# beovox-poe.net
KiCad netlist of a schematic drawn in Altium Designer
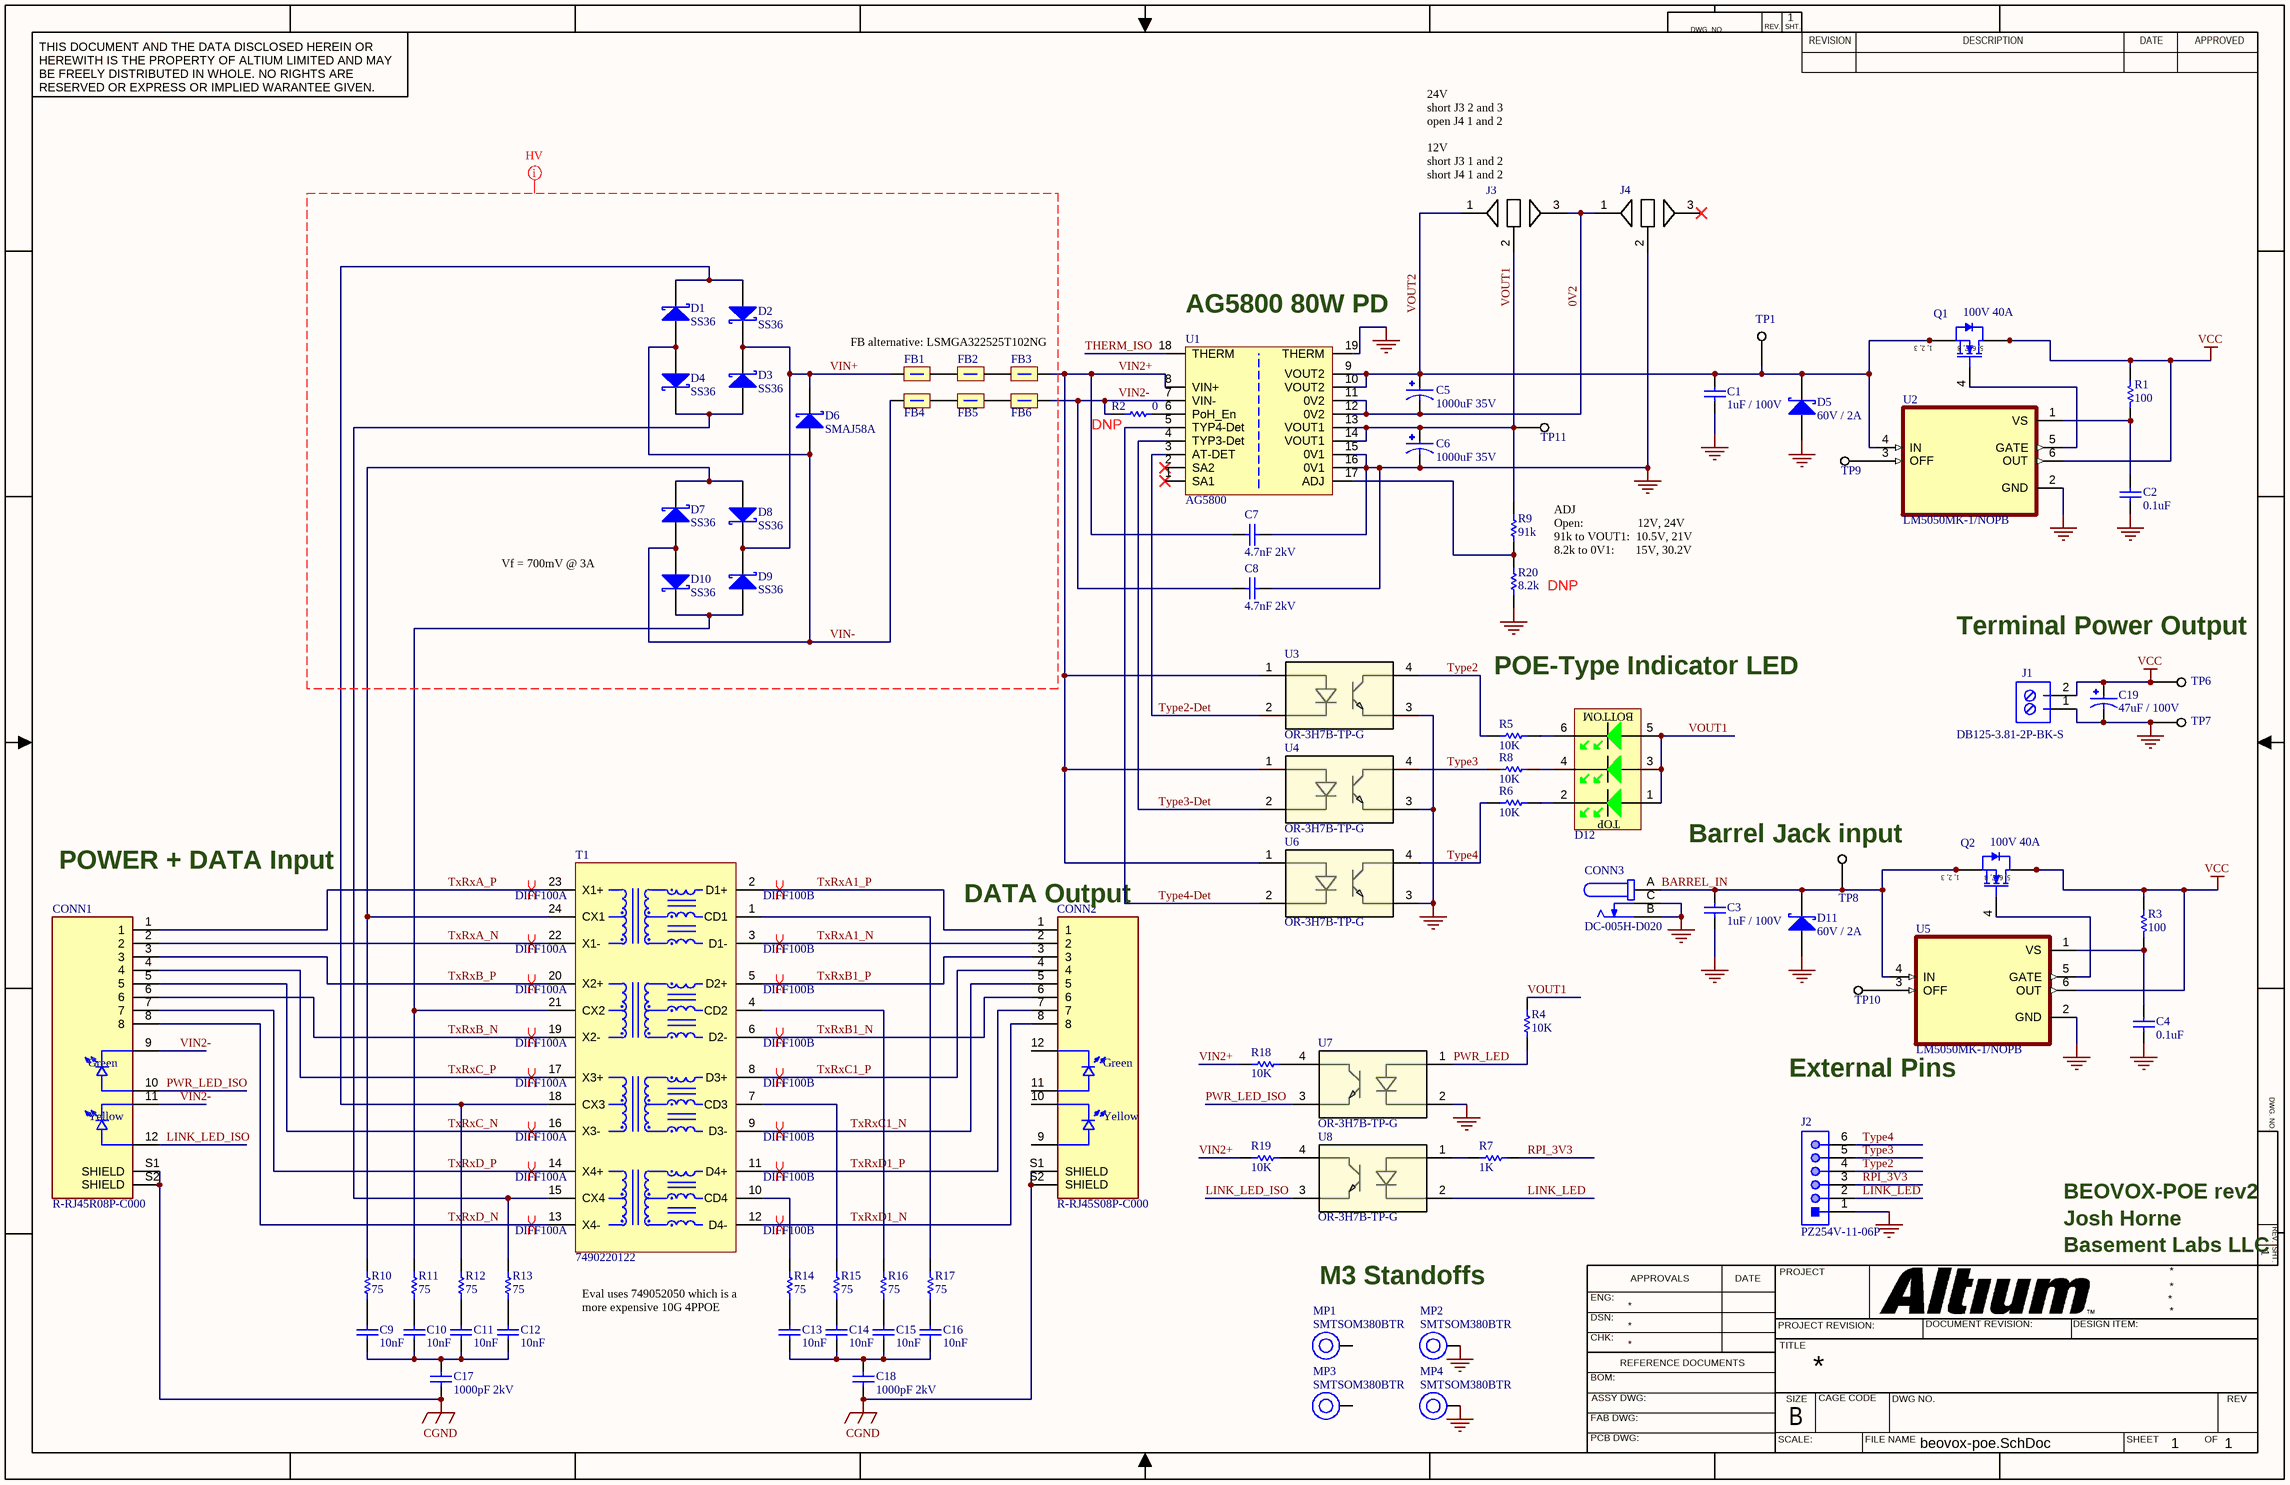
[diagram p0: beovox-poe.SchDoc]

(export (version "E")
  (design (tool "Eeschema 10.0.6"))
  (components
    (comp (ref "C1")
      (value "1uF / 100V")
      (footprint "CAP_1210")
      (description "1210 1 uF 100 V ±10% Tolerance X7R SMT Multilayer Ceramic Capacitor")
      (fields
        (field (name "MANUFACTURER") "Murata")
        (field (name "MANUFACTURER PART NUMBER") "GRM32ER72A105KA01L")
      )
      (libsource (lib "josh-lib") (part "GRM32ER72A105KA01L"))
    )
    (comp (ref "C2")
      (value "0.1uF")
      (footprint "CAP_0603_SK")
      (description "0603 0.1 uF 100 V ±10% Tolerance X7R Multilayer Ceramic Capacitor")
      (fields
        (field (name "MANUFACTURER") "Yageo")
        (field (name "MANUFACTURER PART NUMBER") "CC0603KRX7R0BB104")
      )
      (libsource (lib "josh-lib") (part "CC0603KRX7R0BB104"))
    )
    (comp (ref "C3")
      (value "1uF / 100V")
      (footprint "CAP_1210")
      (description "1210 1 uF 100 V ±10% Tolerance X7R SMT Multilayer Ceramic Capacitor")
      (fields
        (field (name "MANUFACTURER") "Murata")
        (field (name "MANUFACTURER PART NUMBER") "GRM32ER72A105KA01L")
      )
      (libsource (lib "josh-lib") (part "GRM32ER72A105KA01L"))
    )
    (comp (ref "C4")
      (value "0.1uF")
      (footprint "CAP_0603_SK")
      (description "0603 0.1 uF 100 V ±10% Tolerance X7R Multilayer Ceramic Capacitor")
      (fields
        (field (name "MANUFACTURER") "Yageo")
        (field (name "MANUFACTURER PART NUMBER") "CC0603KRX7R0BB104")
      )
      (libsource (lib "josh-lib") (part "CC0603KRX7R0BB104"))
    )
    (comp (ref "C5")
      (value "1000uF 35V")
      (footprint "CAP_TH_5_10X20")
      (description "1000uF 35V ±20% Plugin,D10xL20mm Aluminum Electrolytic Capacitors - Leaded ROHS")
      (fields
        (field (name "MANUFACTURER") "AISHI")
        (field (name "MANUFACTURER PART NUMBER") "ERR1VM102G20OT")
      )
      (libsource (lib "josh-lib") (part "ERR1VM102G20OT"))
    )
    (comp (ref "C6")
      (value "1000uF 35V")
      (footprint "CAP_TH_5_10X20")
      (description "1000uF 35V ±20% Plugin,D10xL20mm Aluminum Electrolytic Capacitors - Leaded ROHS")
      (fields
        (field (name "MANUFACTURER") "AISHI")
        (field (name "MANUFACTURER PART NUMBER") "ERR1VM102G20OT")
      )
      (libsource (lib "josh-lib") (part "ERR1VM102G20OT"))
    )
    (comp (ref "C7")
      (value "4.7nF 2kV")
      (footprint "CAP_1206_SK")
      (description "2kV 4700pF X7R ±10% 1206 Multilayer Ceramic Capacitors MLCC - SMD/SMT ROHS")
      (fields
        (field (name "MANUFACTURER") "FH (Guangdong Fenghua Advanced Tech)")
        (field (name "MANUFACTURER PART NUMBER") "1206B472K202NT")
      )
      (libsource (lib "josh-lib") (part "1206B472K202NT"))
    )
    (comp (ref "C8")
      (value "4.7nF 2kV")
      (footprint "CAP_1206_SK")
      (description "2kV 4700pF X7R ±10% 1206 Multilayer Ceramic Capacitors MLCC - SMD/SMT ROHS")
      (fields
        (field (name "MANUFACTURER") "FH (Guangdong Fenghua Advanced Tech)")
        (field (name "MANUFACTURER PART NUMBER") "1206B472K202NT")
      )
      (libsource (lib "josh-lib") (part "1206B472K202NT"))
    )
    (comp (ref "C9")
      (value "10nF")
      (footprint "CAP_0603_SK")
      (description "Multilayer Ceramic Capacitor, 0.01 F, 10%, X7R, 100 V, 0603 [1608 Metric] Rohs Compliant: Yes")
      (fields
        (field (name "MANUFACTURER") "Walsin Technologies")
        (field (name "MANUFACTURER PART NUMBER") "0603B103K101CT")
      )
      (libsource (lib "josh-lib") (part "0603B103K101CT"))
    )
    (comp (ref "C10")
      (value "10nF")
      (footprint "CAP_0603_SK")
      (description "Multilayer Ceramic Capacitor, 0.01 F, 10%, X7R, 100 V, 0603 [1608 Metric] Rohs Compliant: Yes")
      (fields
        (field (name "MANUFACTURER") "Walsin Technologies")
        (field (name "MANUFACTURER PART NUMBER") "0603B103K101CT")
      )
      (libsource (lib "josh-lib") (part "0603B103K101CT"))
    )
    (comp (ref "C11")
      (value "10nF")
      (footprint "CAP_0603_SK")
      (description "Multilayer Ceramic Capacitor, 0.01 F, 10%, X7R, 100 V, 0603 [1608 Metric] Rohs Compliant: Yes")
      (fields
        (field (name "MANUFACTURER") "Walsin Technologies")
        (field (name "MANUFACTURER PART NUMBER") "0603B103K101CT")
      )
      (libsource (lib "josh-lib") (part "0603B103K101CT"))
    )
    (comp (ref "C12")
      (value "10nF")
      (footprint "CAP_0603_SK")
      (description "Multilayer Ceramic Capacitor, 0.01 F, 10%, X7R, 100 V, 0603 [1608 Metric] Rohs Compliant: Yes")
      (fields
        (field (name "MANUFACTURER") "Walsin Technologies")
        (field (name "MANUFACTURER PART NUMBER") "0603B103K101CT")
      )
      (libsource (lib "josh-lib") (part "0603B103K101CT"))
    )
    (comp (ref "C13")
      (value "10nF")
      (footprint "CAP_0603_SK")
      (description "Multilayer Ceramic Capacitor, 0.01 F, 10%, X7R, 100 V, 0603 [1608 Metric] Rohs Compliant: Yes")
      (fields
        (field (name "MANUFACTURER") "Walsin Technologies")
        (field (name "MANUFACTURER PART NUMBER") "0603B103K101CT")
      )
      (libsource (lib "josh-lib") (part "0603B103K101CT"))
    )
    (comp (ref "C14")
      (value "10nF")
      (footprint "CAP_0603_SK")
      (description "Multilayer Ceramic Capacitor, 0.01 F, 10%, X7R, 100 V, 0603 [1608 Metric] Rohs Compliant: Yes")
      (fields
        (field (name "MANUFACTURER") "Walsin Technologies")
        (field (name "MANUFACTURER PART NUMBER") "0603B103K101CT")
      )
      (libsource (lib "josh-lib") (part "0603B103K101CT"))
    )
    (comp (ref "C15")
      (value "10nF")
      (footprint "CAP_0603_SK")
      (description "Multilayer Ceramic Capacitor, 0.01 F, 10%, X7R, 100 V, 0603 [1608 Metric] Rohs Compliant: Yes")
      (fields
        (field (name "MANUFACTURER") "Walsin Technologies")
        (field (name "MANUFACTURER PART NUMBER") "0603B103K101CT")
      )
      (libsource (lib "josh-lib") (part "0603B103K101CT"))
    )
    (comp (ref "C16")
      (value "10nF")
      (footprint "CAP_0603_SK")
      (description "Multilayer Ceramic Capacitor, 0.01 F, 10%, X7R, 100 V, 0603 [1608 Metric] Rohs Compliant: Yes")
      (fields
        (field (name "MANUFACTURER") "Walsin Technologies")
        (field (name "MANUFACTURER PART NUMBER") "0603B103K101CT")
      )
      (libsource (lib "josh-lib") (part "0603B103K101CT"))
    )
    (comp (ref "C17")
      (value "1000pF 2kV")
      (footprint "CAP_1206_SK")
      (description "Multilayer Ceramic Capacitor, 1000 pF, 2000 V, ± 10%, X7R, 1206 [3216 Metric]")
      (fields
        (field (name "MANUFACTURER") "Yageo")
        (field (name "MANUFACTURER PART NUMBER") "CC1206KKX7RDBB102")
      )
      (libsource (lib "josh-lib") (part "CC1206KKX7RDBB102"))
    )
    (comp (ref "C18")
      (value "1000pF 2kV")
      (footprint "CAP_1206_SK")
      (description "Multilayer Ceramic Capacitor, 1000 pF, 2000 V, ± 10%, X7R, 1206 [3216 Metric]")
      (fields
        (field (name "MANUFACTURER") "Yageo")
        (field (name "MANUFACTURER PART NUMBER") "CC1206KKX7RDBB102")
      )
      (libsource (lib "josh-lib") (part "CC1206KKX7RDBB102"))
    )
    (comp (ref "C19")
      (value "47uF / 100V")
      (footprint "CAP_TH_3.5_8_12")
      (description "47uF 100V ±20% Plugin,D8xL12mm Aluminum Electrolytic Capacitors - Leaded ROHS")
      (fields
        (field (name "MANUFACTURER") "AISHI(Aihua Group)")
        (field (name "MANUFACTURER PART NUMBER") "ERS1KM470F12OT")
      )
      (libsource (lib "josh-lib") (part "ERS1KM470F12OT"))
    )
    (comp (ref "CONN1")
      (value "R-RJ45R08P-C000")
      (footprint "R-RJ45R08P-C000")
      (fields (field (name "MANUFACTURER") "Ckmtw"))
      (libsource (lib "josh-lib") (part "R-RJ45R08P-C000"))
    )
    (comp (ref "CONN2")
      (value "R-RJ45S08P-C000")
      (footprint "CONN_RJ45_R-RJ45S08P-C000")
      (fields (field (name "MANUFACTURER") "Ckmtw(Shenzhen Cankemeng)"))
      (libsource (lib "josh-lib") (part "R-RJ45S08P-C000"))
    )
    (comp (ref "CONN3")
      (value "DC-005H-D020")
      (footprint "TENSILITY_54-00166")
      (description "Right-Angle DC Power Receptacle -30℃~+85℃ 2mm 5.8mm 7A 35V Plugin AC/DC Power Connectors ROHS")
      (fields (field (name "MANUFACTURER") "G-Switch"))
      (libsource (lib "josh-lib") (part "DC-005H-D020"))
    )
    (comp (ref "D1")
      (value "SS36")
      (footprint "DIOD-SMA-2_V")
      (description "60V 700mV@3A 3A SMA(DO-214AC) Schottky Barrier Diodes (SBD) ROHS")
      (fields (field (name "MANUFACTURER") "MDD"))
      (libsource (lib "josh-lib") (part "SS36"))
    )
    (comp (ref "D2")
      (value "SS36")
      (footprint "DIOD-SMA-2_V")
      (description "60V 700mV@3A 3A SMA(DO-214AC) Schottky Barrier Diodes (SBD) ROHS")
      (fields (field (name "MANUFACTURER") "MDD"))
      (libsource (lib "josh-lib") (part "SS36"))
    )
    (comp (ref "D3")
      (value "SS36")
      (footprint "DIOD-SMA-2_V")
      (description "60V 700mV@3A 3A SMA(DO-214AC) Schottky Barrier Diodes (SBD) ROHS")
      (fields (field (name "MANUFACTURER") "MDD"))
      (libsource (lib "josh-lib") (part "SS36"))
    )
    (comp (ref "D4")
      (value "SS36")
      (footprint "DIOD-SMA-2_V")
      (description "60V 700mV@3A 3A SMA(DO-214AC) Schottky Barrier Diodes (SBD) ROHS")
      (fields (field (name "MANUFACTURER") "MDD"))
      (libsource (lib "josh-lib") (part "SS36"))
    )
    (comp (ref "D5")
      (value "60V / 2A")
      (footprint "DIOD-B360A_V")
      (description "VR=60V IF=2A 200pF")
      (fields (field (name "MANUFACTURER") "Diodes") (field (name "MANUFACTURER PART NUMBER") "B260-13-F"))
      (libsource (lib "josh-lib") (part "B260-13-F"))
    )
    (comp (ref "D6")
      (value "SMAJ58A")
      (footprint "DIOD-SMA-2_V")
      (description "4.3A 400W 93.6V 64.4V 58V SMA(DO-214AC) TVS ROHS")
      (fields (field (name "MANUFACTURER") "GOODWORK"))
      (libsource (lib "josh-lib") (part "SMAJ58A"))
    )
    (comp (ref "D7")
      (value "SS36")
      (footprint "DIOD-SMA-2_V")
      (description "60V 700mV@3A 3A SMA(DO-214AC) Schottky Barrier Diodes (SBD) ROHS")
      (fields (field (name "MANUFACTURER") "MDD"))
      (libsource (lib "josh-lib") (part "SS36"))
    )
    (comp (ref "D8")
      (value "SS36")
      (footprint "DIOD-SMA-2_V")
      (description "60V 700mV@3A 3A SMA(DO-214AC) Schottky Barrier Diodes (SBD) ROHS")
      (fields (field (name "MANUFACTURER") "MDD"))
      (libsource (lib "josh-lib") (part "SS36"))
    )
    (comp (ref "D9")
      (value "SS36")
      (footprint "DIOD-SMA-2_V")
      (description "60V 700mV@3A 3A SMA(DO-214AC) Schottky Barrier Diodes (SBD) ROHS")
      (fields (field (name "MANUFACTURER") "MDD"))
      (libsource (lib "josh-lib") (part "SS36"))
    )
    (comp (ref "D10")
      (value "SS36")
      (footprint "DIOD-SMA-2_V")
      (description "60V 700mV@3A 3A SMA(DO-214AC) Schottky Barrier Diodes (SBD) ROHS")
      (fields (field (name "MANUFACTURER") "MDD"))
      (libsource (lib "josh-lib") (part "SS36"))
    )
    (comp (ref "D11")
      (value "60V / 2A")
      (footprint "DIOD-B360A_V")
      (description "VR=60V IF=2A 200pF")
      (fields (field (name "MANUFACTURER") "Diodes") (field (name "MANUFACTURER PART NUMBER") "B260-13-F"))
      (libsource (lib "josh-lib") (part "B260-13-F"))
    )
    (comp (ref "D12")
      (value "3 Diode Vertical LED Green")
      (footprint "MHK33147CGBTD")
      (description "20mA 30mcd 雾状绿透镜 -40℃~+85℃ 568nm Green 60° 2.6V DIP-6-2.54mm Light Emitting Diodes (LED) ROHS")
      (fields
        (field (name "MANUFACTURER") "MEIHUA")
        (field (name "MANUFACTURER PART NUMBER") "MHK33147CGBTD")
      )
      (libsource (lib "josh-lib") (part "MHK33147CGBTD"))
    )
    (comp (ref "FB1")
      (value "MPZ2012S601AT000")
      (footprint "FB0805")
      (description "Ferrite Beads Multi-Layer Power 600Ohm 25% 100MHz 2A 100mOhm DCR 0805 T/R")
      (fields (field (name "MANUFACTURER") "TDK") (field (name "TOLERANCE") "25%"))
      (libsource (lib "josh-lib") (part "MPZ2012S601AT000"))
    )
    (comp (ref "FB2")
      (value "MPZ2012S601AT000")
      (footprint "FB0805")
      (description "Ferrite Beads Multi-Layer Power 600Ohm 25% 100MHz 2A 100mOhm DCR 0805 T/R")
      (fields (field (name "MANUFACTURER") "TDK") (field (name "TOLERANCE") "25%"))
      (libsource (lib "josh-lib") (part "MPZ2012S601AT000"))
    )
    (comp (ref "FB3")
      (value "MPZ2012S601AT000")
      (footprint "FB0805")
      (description "Ferrite Beads Multi-Layer Power 600Ohm 25% 100MHz 2A 100mOhm DCR 0805 T/R")
      (fields (field (name "MANUFACTURER") "TDK") (field (name "TOLERANCE") "25%"))
      (libsource (lib "josh-lib") (part "MPZ2012S601AT000"))
    )
    (comp (ref "FB4")
      (value "MPZ2012S601AT000")
      (footprint "FB0805")
      (description "Ferrite Beads Multi-Layer Power 600Ohm 25% 100MHz 2A 100mOhm DCR 0805 T/R")
      (fields (field (name "MANUFACTURER") "TDK") (field (name "TOLERANCE") "25%"))
      (libsource (lib "josh-lib") (part "MPZ2012S601AT000"))
    )
    (comp (ref "FB5")
      (value "MPZ2012S601AT000")
      (footprint "FB0805")
      (description "Ferrite Beads Multi-Layer Power 600Ohm 25% 100MHz 2A 100mOhm DCR 0805 T/R")
      (fields (field (name "MANUFACTURER") "TDK") (field (name "TOLERANCE") "25%"))
      (libsource (lib "josh-lib") (part "MPZ2012S601AT000"))
    )
    (comp (ref "FB6")
      (value "MPZ2012S601AT000")
      (footprint "FB0805")
      (description "Ferrite Beads Multi-Layer Power 600Ohm 25% 100MHz 2A 100mOhm DCR 0805 T/R")
      (fields (field (name "MANUFACTURER") "TDK") (field (name "TOLERANCE") "25%"))
      (libsource (lib "josh-lib") (part "MPZ2012S601AT000"))
    )
    (comp (ref "J1")
      (value "DB125-3.81-2P-BK-S")
      (footprint "TERM_2x1_3.81_BLK")
      (description "1x2P 10A -40℃~+105℃ 300V Black 16~26 Straight 3.81mm 0.5~1 1 2 Plugin,P=3.81mm Screw terminal ROHS")
      (fields (field (name "MANUFACTURER") "Dorabo"))
      (libsource (lib "josh-lib") (part "DB125-3.81-2P-BK-S"))
    )
    (comp (ref "J2")
      (value "PZ254V-11-06P")
      (footprint "HDR_MALE_1X6_2.54")
      (fields (field (name "MANUFACTURER") "XFCN"))
      (libsource (lib "josh-lib") (part "PZ254V-11-06P"))
    )
    (comp (ref "J3")
      (value "JUMPER")
      (footprint "SOLDER_JUMPER_3 large")
      (libsource (lib "josh-lib") (part "Solder_Jumper_3"))
    )
    (comp (ref "J4")
      (value "JUMPER")
      (footprint "SOLDER_JUMPER_3 large")
      (libsource (lib "josh-lib") (part "Solder_Jumper_3"))
    )
    (comp (ref "MP1")
      (value "SMTSOM380BTR")
      (footprint "SMTSOM380_PlatedScrew")
      (description "M3 Round Nut 8mm height")
      (fields (field (name "MANUFACTURER") "YIYUAN"))
      (libsource (lib "josh-lib") (part "SMTSOM380BTR"))
    )
    (comp (ref "MP2")
      (value "SMTSOM380BTR")
      (footprint "SMTSOM380_PlatedScrew")
      (description "M3 Round Nut 8mm height")
      (fields (field (name "MANUFACTURER") "YIYUAN"))
      (libsource (lib "josh-lib") (part "SMTSOM380BTR"))
    )
    (comp (ref "MP3")
      (value "SMTSOM380BTR")
      (footprint "SMTSOM380_PlatedScrew")
      (description "M3 Round Nut 8mm height")
      (fields (field (name "MANUFACTURER") "YIYUAN"))
      (libsource (lib "josh-lib") (part "SMTSOM380BTR"))
    )
    (comp (ref "MP4")
      (value "SMTSOM380BTR")
      (footprint "SMTSOM380_PlatedScrew")
      (description "M3 Round Nut 8mm height")
      (fields (field (name "MANUFACTURER") "YIYUAN"))
      (libsource (lib "josh-lib") (part "SMTSOM380BTR"))
    )
    (comp (ref "Q1")
      (value "100V 40A")
      (footprint "TRANS_8PowerTDFN")
      (description "BSZ097xx Series 100 V 40 A 9.7 mOhm OptiMOS5 Power-MOSFET - TSDSON-8 FL")
      (fields
        (field (name "MANUFACTURER") "Infineon")
        (field (name "MANUFACTURER PART NUMBER") "BSZ097N10NS5ATMA1")
      )
      (libsource (lib "josh-lib") (part "BSZ097N10NS5ATMA1"))
    )
    (comp (ref "Q2")
      (value "100V 40A")
      (footprint "TRANS_8PowerTDFN")
      (description "BSZ097xx Series 100 V 40 A 9.7 mOhm OptiMOS5 Power-MOSFET - TSDSON-8 FL")
      (fields
        (field (name "MANUFACTURER") "Infineon")
        (field (name "MANUFACTURER PART NUMBER") "BSZ097N10NS5ATMA1")
      )
      (libsource (lib "josh-lib") (part "BSZ097N10NS5ATMA1"))
    )
    (comp (ref "R1")
      (value "100")
      (footprint "RES_0603")
      (description "Res Thick Film 0603 100 Ohm 1% 1/10W ±100ppm/°C Molded SMD Paper T/R")
      (fields
        (field (name "MANUFACTURER") "Yageo")
        (field (name "MANUFACTURER PART NUMBER") "RC0603FR-07100RL")
      )
      (libsource (lib "josh-lib") (part "RC0603FR-07100RL"))
    )
    (comp (ref "R2")
      (value "0")
      (footprint "RES_0805")
      (description "Surface Mount Thick Film Resistor, RC Series, 125 mW, - 5%, 150 V, 0805 [2012 Metric]")
      (fields
        (field (name "MANUFACTURER") "Yageo")
        (field (name "MANUFACTURER PART NUMBER") "RC0805JR-070RL")
      )
      (libsource (lib "josh-lib") (part "RC0805JR-070RL"))
    )
    (comp (ref "R3")
      (value "100")
      (footprint "RES_0603")
      (description "Res Thick Film 0603 100 Ohm 1% 1/10W ±100ppm/°C Molded SMD Paper T/R")
      (fields
        (field (name "MANUFACTURER") "Yageo")
        (field (name "MANUFACTURER PART NUMBER") "RC0603FR-07100RL")
      )
      (libsource (lib "josh-lib") (part "RC0603FR-07100RL"))
    )
    (comp (ref "R4")
      (value "10K")
      (footprint "RES_0603")
      (description "RES SMD 10K OHM 1% 1/10W 0603")
      (fields
        (field (name "MANUFACTURER") "Panasonic")
        (field (name "MANUFACTURER PART NUMBER") "ERJ3EKF1002V")
      )
      (libsource (lib "josh-lib") (part "ERJ3EKF1002V"))
    )
    (comp (ref "R5")
      (value "10K")
      (footprint "RES_0603")
      (description "RES SMD 10K OHM 1% 1/10W 0603")
      (fields
        (field (name "MANUFACTURER") "Panasonic")
        (field (name "MANUFACTURER PART NUMBER") "ERJ3EKF1002V")
      )
      (libsource (lib "josh-lib") (part "ERJ3EKF1002V"))
    )
    (comp (ref "R6")
      (value "10K")
      (footprint "RES_0603")
      (description "RES SMD 10K OHM 1% 1/10W 0603")
      (fields
        (field (name "MANUFACTURER") "Panasonic")
        (field (name "MANUFACTURER PART NUMBER") "ERJ3EKF1002V")
      )
      (libsource (lib "josh-lib") (part "ERJ3EKF1002V"))
    )
    (comp (ref "R7")
      (value "1K")
      (footprint "RES_0603")
      (description "Res Thick Film 0603 1K Ohm 1% 1/10W ±100ppm/°C Molded SMD SMD Paper T/R")
      (fields
        (field (name "MANUFACTURER") "Yageo")
        (field (name "MANUFACTURER PART NUMBER") "RC0603FR-071KL")
      )
      (libsource (lib "josh-lib") (part "RC0603FR-071KL"))
    )
    (comp (ref "R8")
      (value "10K")
      (footprint "RES_0603")
      (description "RES SMD 10K OHM 1% 1/10W 0603")
      (fields
        (field (name "MANUFACTURER") "Panasonic")
        (field (name "MANUFACTURER PART NUMBER") "ERJ3EKF1002V")
      )
      (libsource (lib "josh-lib") (part "ERJ3EKF1002V"))
    )
    (comp (ref "R9")
      (value "91k")
      (footprint "RES_0603")
      (description "SMD Chip Resistor, 91 kOhm, ± 1%, 100 mW, 0603 [1608 Metric], Thick Film, General Purpose")
      (fields
        (field (name "MANUFACTURER") "Yageo")
        (field (name "MANUFACTURER PART NUMBER") "RC0603FR-0791KL")
      )
      (libsource (lib "josh-lib") (part "RC0603FR-0791KL"))
    )
    (comp (ref "R10")
      (value "75")
      (footprint "RES_0603")
      (description "SMD Chip Resistor, 75 Ohm, ± 1%, 100 mW, 0603 [1608 Metric], Thick Film, General Purpose")
      (fields
        (field (name "MANUFACTURER") "Yageo")
        (field (name "MANUFACTURER PART NUMBER") "RC0603FR-0775RL")
      )
      (libsource (lib "josh-lib") (part "RC0603FR-0775RL"))
    )
    (comp (ref "R11")
      (value "75")
      (footprint "RES_0603")
      (description "SMD Chip Resistor, 75 Ohm, ± 1%, 100 mW, 0603 [1608 Metric], Thick Film, General Purpose")
      (fields
        (field (name "MANUFACTURER") "Yageo")
        (field (name "MANUFACTURER PART NUMBER") "RC0603FR-0775RL")
      )
      (libsource (lib "josh-lib") (part "RC0603FR-0775RL"))
    )
    (comp (ref "R12")
      (value "75")
      (footprint "RES_0603")
      (description "SMD Chip Resistor, 75 Ohm, ± 1%, 100 mW, 0603 [1608 Metric], Thick Film, General Purpose")
      (fields
        (field (name "MANUFACTURER") "Yageo")
        (field (name "MANUFACTURER PART NUMBER") "RC0603FR-0775RL")
      )
      (libsource (lib "josh-lib") (part "RC0603FR-0775RL"))
    )
    (comp (ref "R13")
      (value "75")
      (footprint "RES_0603")
      (description "SMD Chip Resistor, 75 Ohm, ± 1%, 100 mW, 0603 [1608 Metric], Thick Film, General Purpose")
      (fields
        (field (name "MANUFACTURER") "Yageo")
        (field (name "MANUFACTURER PART NUMBER") "RC0603FR-0775RL")
      )
      (libsource (lib "josh-lib") (part "RC0603FR-0775RL"))
    )
    (comp (ref "R14")
      (value "75")
      (footprint "RES_0603")
      (description "SMD Chip Resistor, 75 Ohm, ± 1%, 100 mW, 0603 [1608 Metric], Thick Film, General Purpose")
      (fields
        (field (name "MANUFACTURER") "Yageo")
        (field (name "MANUFACTURER PART NUMBER") "RC0603FR-0775RL")
      )
      (libsource (lib "josh-lib") (part "RC0603FR-0775RL"))
    )
    (comp (ref "R15")
      (value "75")
      (footprint "RES_0603")
      (description "SMD Chip Resistor, 75 Ohm, ± 1%, 100 mW, 0603 [1608 Metric], Thick Film, General Purpose")
      (fields
        (field (name "MANUFACTURER") "Yageo")
        (field (name "MANUFACTURER PART NUMBER") "RC0603FR-0775RL")
      )
      (libsource (lib "josh-lib") (part "RC0603FR-0775RL"))
    )
    (comp (ref "R16")
      (value "75")
      (footprint "RES_0603")
      (description "SMD Chip Resistor, 75 Ohm, ± 1%, 100 mW, 0603 [1608 Metric], Thick Film, General Purpose")
      (fields
        (field (name "MANUFACTURER") "Yageo")
        (field (name "MANUFACTURER PART NUMBER") "RC0603FR-0775RL")
      )
      (libsource (lib "josh-lib") (part "RC0603FR-0775RL"))
    )
    (comp (ref "R17")
      (value "75")
      (footprint "RES_0603")
      (description "SMD Chip Resistor, 75 Ohm, ± 1%, 100 mW, 0603 [1608 Metric], Thick Film, General Purpose")
      (fields
        (field (name "MANUFACTURER") "Yageo")
        (field (name "MANUFACTURER PART NUMBER") "RC0603FR-0775RL")
      )
      (libsource (lib "josh-lib") (part "RC0603FR-0775RL"))
    )
    (comp (ref "R18")
      (value "10K")
      (footprint "RES_0603")
      (description "RES SMD 10K OHM 1% 1/10W 0603")
      (fields
        (field (name "MANUFACTURER") "Panasonic")
        (field (name "MANUFACTURER PART NUMBER") "ERJ3EKF1002V")
      )
      (libsource (lib "josh-lib") (part "ERJ3EKF1002V"))
    )
    (comp (ref "R19")
      (value "10K")
      (footprint "RES_0603")
      (description "RES SMD 10K OHM 1% 1/10W 0603")
      (fields
        (field (name "MANUFACTURER") "Panasonic")
        (field (name "MANUFACTURER PART NUMBER") "ERJ3EKF1002V")
      )
      (libsource (lib "josh-lib") (part "ERJ3EKF1002V"))
    )
    (comp (ref "R20")
      (value "8.2k")
      (footprint "RES_0603")
      (description "Res Thick Film 0603 8.2K Ohm 1% 0.1W(1/10W) ±100ppm/C Pad SMD T/R")
      (fields
        (field (name "MANUFACTURER") "Yageo")
        (field (name "MANUFACTURER PART NUMBER") "RC0603FR-078K2L")
      )
      (libsource (lib "josh-lib") (part "RC0603FR-078K2L"))
    )
    (comp (ref "T1")
      (value "7490220122")
      (footprint "XFMR_7490220122")
      (description "WE-LAN 10/100/1000 Base-T SMT Transformer 1 Port")
      (fields (field (name "MANUFACTURER") "Wurth Electronics"))
      (libsource (lib "josh-lib") (part "7490220122"))
    )
    (comp (ref "TP1") (value "TP") (footprint "Test_Point") (libsource (lib "josh-lib") (part "Test_Point")))
    (comp (ref "TP6") (value "TP") (footprint "Test_Point") (libsource (lib "josh-lib") (part "Test_Point")))
    (comp (ref "TP7") (value "TP") (footprint "Test_Point") (libsource (lib "josh-lib") (part "Test_Point")))
    (comp (ref "TP8") (value "TP") (footprint "Test_Point") (libsource (lib "josh-lib") (part "Test_Point")))
    (comp (ref "TP9") (value "TP") (footprint "Test_Point") (libsource (lib "josh-lib") (part "Test_Point")))
    (comp (ref "TP10") (value "TP") (footprint "Test_Point") (libsource (lib "josh-lib") (part "Test_Point")))
    (comp (ref "TP11") (value "TP") (footprint "Test_Point") (libsource (lib "josh-lib") (part "Test_Point")))
    (comp (ref "U1")
      (value "AG5800")
      (footprint "AG5800")
      (description "IEEE802.3bt 4-Pair PD Module - works with AG6800")
      (fields (field (name "MANUFACTURER") "Silvertel"))
      (libsource (lib "josh-lib") (part "AG5800"))
    )
    (comp (ref "U2")
      (value "LM5050MK-1/NOPB")
      (footprint "SOT95P280X110-6N")
      (description "IC OR CTRLR N+1 6SOT")
      (fields (field (name "MANUFACTURER") "TI National Semiconductor"))
      (libsource (lib "josh-lib") (part "LM5050MK-1/NOPB"))
    )
    (comp (ref "U3")
      (value "OR-3H7B-TP-G")
      (footprint "SOIC_(B)(TA)-VG_EVS")
      (description "80V 3750V 50mA 0.4V@2.4mA,8mA 1 6V 1.2V DC SOP-4-1.27mm Optocouplers - Phototransistor Output ROHS")
      (fields (field (name "MANUFACTURER") "Orient"))
      (libsource (lib "josh-lib") (part "OR-3H7B-TP-G"))
    )
    (comp (ref "U4")
      (value "OR-3H7B-TP-G")
      (footprint "SOIC_(B)(TA)-VG_EVS")
      (description "80V 3750V 50mA 0.4V@2.4mA,8mA 1 6V 1.2V DC SOP-4-1.27mm Optocouplers - Phototransistor Output ROHS")
      (fields (field (name "MANUFACTURER") "Orient"))
      (libsource (lib "josh-lib") (part "OR-3H7B-TP-G"))
    )
    (comp (ref "U5")
      (value "LM5050MK-1/NOPB")
      (footprint "SOT95P280X110-6N")
      (description "IC OR CTRLR N+1 6SOT")
      (fields (field (name "MANUFACTURER") "TI National Semiconductor"))
      (libsource (lib "josh-lib") (part "LM5050MK-1/NOPB"))
    )
    (comp (ref "U6")
      (value "OR-3H7B-TP-G")
      (footprint "SOIC_(B)(TA)-VG_EVS")
      (description "80V 3750V 50mA 0.4V@2.4mA,8mA 1 6V 1.2V DC SOP-4-1.27mm Optocouplers - Phototransistor Output ROHS")
      (fields (field (name "MANUFACTURER") "Orient"))
      (libsource (lib "josh-lib") (part "OR-3H7B-TP-G"))
    )
    (comp (ref "U7")
      (value "OR-3H7B-TP-G")
      (footprint "SOIC_(B)(TA)-VG_EVS")
      (description "80V 3750V 50mA 0.4V@2.4mA,8mA 1 6V 1.2V DC SOP-4-1.27mm Optocouplers - Phototransistor Output ROHS")
      (fields (field (name "MANUFACTURER") "Orient"))
      (libsource (lib "") (part "OR-3H7B-TP-G_1"))
    )
    (comp (ref "U8")
      (value "OR-3H7B-TP-G")
      (footprint "SOIC_(B)(TA)-VG_EVS")
      (description "80V 3750V 50mA 0.4V@2.4mA,8mA 1 6V 1.2V DC SOP-4-1.27mm Optocouplers - Phototransistor Output ROHS")
      (fields (field (name "MANUFACTURER") "Orient"))
      (libsource (lib "") (part "OR-3H7B-TP-G_1"))
    )
  )
  (nets
    (net (code "1") (name "/0V2") (class "Default")
      (node (ref "C5") (pin "N") (pinfunction "N_N") (pintype "passive"))
      (node (ref "J3") (pin "3") (pinfunction "3_3") (pintype "passive"))
      (node (ref "J4") (pin "1") (pinfunction "1_1") (pintype "passive"))
      (node (ref "U1") (pin "11") (pinfunction "0V2_11") (pintype "passive"))
      (node (ref "U1") (pin "12") (pinfunction "0V2_12") (pintype "passive"))
    )
    (net (code "2") (name "/BARREL_IN") (class "Default")
      (node (ref "C3") (pin "2") (pinfunction "2_2") (pintype "passive"))
      (node (ref "CONN3") (pin "A") (pinfunction "A_A") (pintype "passive"))
      (node (ref "D11") (pin "2") (pinfunction "K_2") (pintype "passive"))
      (node (ref "Q2") (pin "1") (pinfunction "SOURCE_1") (pintype "passive"))
      (node (ref "Q2") (pin "2") (pinfunction "SOURCE_2") (pintype "passive"))
      (node (ref "Q2") (pin "3") (pinfunction "SOURCE_3") (pintype "passive"))
      (node (ref "TP8") (pin "1") (pinfunction "1_1") (pintype "passive"))
      (node (ref "U5") (pin "4") (pinfunction "IN_4") (pintype "input"))
    )
    (net (code "3") (name "/LINK_LED") (class "Default")
      (node (ref "J2") (pin "2") (pinfunction "2_2") (pintype "passive"))
      (node (ref "U8") (pin "2") (pinfunction "2_2") (pintype "passive"))
    )
    (net (code "4") (name "/LINK_LED_ISO") (class "Default")
      (node (ref "CONN1") (pin "12") (pinfunction "12_12") (pintype "passive"))
      (node (ref "U8") (pin "3") (pinfunction "3_3") (pintype "passive"))
    )
    (net (code "5") (name "/PWR_LED") (class "Default")
      (node (ref "R4") (pin "1") (pinfunction "1_1") (pintype "passive"))
      (node (ref "U7") (pin "1") (pinfunction "1_1") (pintype "passive"))
    )
    (net (code "6") (name "/PWR_LED_ISO") (class "Default")
      (node (ref "CONN1") (pin "10") (pinfunction "10_10") (pintype "passive"))
      (node (ref "U7") (pin "3") (pinfunction "3_3") (pintype "passive"))
    )
    (net (code "7") (name "/RPI_3V3") (class "Default")
      (node (ref "J2") (pin "3") (pinfunction "3_3") (pintype "passive"))
      (node (ref "R7") (pin "1") (pinfunction "1_1") (pintype "passive"))
    )
    (net (code "8") (name "/THERM_ISO") (class "Default")
      (node (ref "U1") (pin "18") (pinfunction "THERM_18") (pintype "passive"))
    )
    (net (code "9") (name "/TxRxA1_N") (class "Default")
      (node (ref "CONN2") (pin "2") (pinfunction "2_2") (pintype "passive"))
      (node (ref "T1") (pin "3") (pinfunction "D1-_3") (pintype "passive"))
    )
    (net (code "10") (name "/TxRxA1_P") (class "Default")
      (node (ref "CONN2") (pin "1") (pinfunction "1_1") (pintype "passive"))
      (node (ref "T1") (pin "2") (pinfunction "D1+_2") (pintype "passive"))
    )
    (net (code "11") (name "/TxRxA_N") (class "Default")
      (node (ref "CONN1") (pin "2") (pinfunction "2_2") (pintype "passive"))
      (node (ref "T1") (pin "22") (pinfunction "X1-_22") (pintype "passive"))
    )
    (net (code "12") (name "/TxRxA_P") (class "Default")
      (node (ref "CONN1") (pin "1") (pinfunction "1_1") (pintype "passive"))
      (node (ref "T1") (pin "23") (pinfunction "X1+_23") (pintype "passive"))
    )
    (net (code "13") (name "/TxRxB1_N") (class "Default")
      (node (ref "CONN2") (pin "6") (pinfunction "6_6") (pintype "passive"))
      (node (ref "T1") (pin "6") (pinfunction "D2-_6") (pintype "passive"))
    )
    (net (code "14") (name "/TxRxB1_P") (class "Default")
      (node (ref "CONN2") (pin "3") (pinfunction "3_3") (pintype "passive"))
      (node (ref "T1") (pin "5") (pinfunction "D2+_5") (pintype "passive"))
    )
    (net (code "15") (name "/TxRxB_N") (class "Default")
      (node (ref "CONN1") (pin "6") (pinfunction "6_6") (pintype "passive"))
      (node (ref "T1") (pin "19") (pinfunction "X2-_19") (pintype "passive"))
    )
    (net (code "16") (name "/TxRxB_P") (class "Default")
      (node (ref "CONN1") (pin "3") (pinfunction "3_3") (pintype "passive"))
      (node (ref "T1") (pin "20") (pinfunction "X2+_20") (pintype "passive"))
    )
    (net (code "17") (name "/TxRxC1_N") (class "Default")
      (node (ref "CONN2") (pin "5") (pinfunction "5_5") (pintype "passive"))
      (node (ref "T1") (pin "9") (pinfunction "D3-_9") (pintype "passive"))
    )
    (net (code "18") (name "/TxRxC1_P") (class "Default")
      (node (ref "CONN2") (pin "4") (pinfunction "4_4") (pintype "passive"))
      (node (ref "T1") (pin "8") (pinfunction "D3+_8") (pintype "passive"))
    )
    (net (code "19") (name "/TxRxC_N") (class "Default")
      (node (ref "CONN1") (pin "5") (pinfunction "5_5") (pintype "passive"))
      (node (ref "T1") (pin "16") (pinfunction "X3-_16") (pintype "passive"))
    )
    (net (code "20") (name "/TxRxC_P") (class "Default")
      (node (ref "CONN1") (pin "4") (pinfunction "4_4") (pintype "passive"))
      (node (ref "T1") (pin "17") (pinfunction "X3+_17") (pintype "passive"))
    )
    (net (code "21") (name "/TxRxD1_N") (class "Default")
      (node (ref "CONN2") (pin "8") (pinfunction "8_8") (pintype "passive"))
      (node (ref "T1") (pin "12") (pinfunction "D4-_12") (pintype "passive"))
    )
    (net (code "22") (name "/TxRxD1_P") (class "Default")
      (node (ref "CONN2") (pin "7") (pinfunction "7_7") (pintype "passive"))
      (node (ref "T1") (pin "11") (pinfunction "D4+_11") (pintype "passive"))
    )
    (net (code "23") (name "/TxRxD_N") (class "Default")
      (node (ref "CONN1") (pin "8") (pinfunction "8_8") (pintype "passive"))
      (node (ref "T1") (pin "13") (pinfunction "X4-_13") (pintype "passive"))
    )
    (net (code "24") (name "/TxRxD_P") (class "Default")
      (node (ref "CONN1") (pin "7") (pinfunction "7_7") (pintype "passive"))
      (node (ref "T1") (pin "14") (pinfunction "X4+_14") (pintype "passive"))
    )
    (net (code "25") (name "/Type2") (class "Default")
      (node (ref "J2") (pin "4") (pinfunction "4_4") (pintype "passive"))
      (node (ref "R5") (pin "2") (pinfunction "2_2") (pintype "passive"))
      (node (ref "U3") (pin "4") (pinfunction "4_4") (pintype "passive"))
    )
    (net (code "26") (name "/Type2-Det") (class "Default")
      (node (ref "U1") (pin "3") (pinfunction "AT-DET_3") (pintype "passive"))
      (node (ref "U3") (pin "2") (pinfunction "2_2") (pintype "passive"))
    )
    (net (code "27") (name "/Type3") (class "Default")
      (node (ref "J2") (pin "5") (pinfunction "5_5") (pintype "passive"))
      (node (ref "R8") (pin "2") (pinfunction "2_2") (pintype "passive"))
      (node (ref "U4") (pin "4") (pinfunction "4_4") (pintype "passive"))
    )
    (net (code "28") (name "/Type3-Det") (class "Default")
      (node (ref "U1") (pin "4") (pinfunction "TYP3-Det_4") (pintype "passive"))
      (node (ref "U4") (pin "2") (pinfunction "2_2") (pintype "passive"))
    )
    (net (code "29") (name "/Type4") (class "Default")
      (node (ref "J2") (pin "6") (pinfunction "6_6") (pintype "passive"))
      (node (ref "R6") (pin "2") (pinfunction "2_2") (pintype "passive"))
      (node (ref "U6") (pin "4") (pinfunction "4_4") (pintype "passive"))
    )
    (net (code "30") (name "/Type4-Det") (class "Default")
      (node (ref "U1") (pin "5") (pinfunction "TYP4-Det_5") (pintype "passive"))
      (node (ref "U6") (pin "2") (pinfunction "2_2") (pintype "passive"))
    )
    (net (code "31") (name "/VIN+") (class "Default")
      (node (ref "D2") (pin "2") (pinfunction "K_2") (pintype "passive"))
      (node (ref "D3") (pin "2") (pinfunction "K_2") (pintype "passive"))
      (node (ref "D6") (pin "2") (pinfunction "K_2") (pintype "passive"))
      (node (ref "D8") (pin "2") (pinfunction "K_2") (pintype "passive"))
      (node (ref "D9") (pin "2") (pinfunction "K_2") (pintype "passive"))
      (node (ref "FB1") (pin "1") (pinfunction "1_1") (pintype "passive"))
    )
    (net (code "32") (name "/VIN-") (class "Default")
      (node (ref "D1") (pin "1") (pinfunction "A_1") (pintype "passive"))
      (node (ref "D10") (pin "1") (pinfunction "A_1") (pintype "passive"))
      (node (ref "D4") (pin "1") (pinfunction "A_1") (pintype "passive"))
      (node (ref "D6") (pin "1") (pinfunction "A_1") (pintype "passive"))
      (node (ref "D7") (pin "1") (pinfunction "A_1") (pintype "passive"))
      (node (ref "FB4") (pin "1") (pinfunction "1_1") (pintype "passive"))
    )
    (net (code "33") (name "/VIN2+") (class "Default")
      (node (ref "C7") (pin "1") (pinfunction "1_1") (pintype "passive"))
      (node (ref "FB3") (pin "2") (pinfunction "2_2") (pintype "passive"))
      (node (ref "R18") (pin "2") (pinfunction "2_2") (pintype "passive"))
      (node (ref "R19") (pin "2") (pinfunction "2_2") (pintype "passive"))
      (node (ref "U1") (pin "8") (pinfunction "VIN+_8") (pintype "passive"))
      (node (ref "U3") (pin "1") (pinfunction "1_1") (pintype "passive"))
      (node (ref "U4") (pin "1") (pinfunction "1_1") (pintype "passive"))
      (node (ref "U6") (pin "1") (pinfunction "1_1") (pintype "passive"))
    )
    (net (code "34") (name "/VIN2-") (class "Default")
      (node (ref "C8") (pin "1") (pinfunction "1_1") (pintype "passive"))
      (node (ref "CONN1") (pin "11") (pinfunction "11_11") (pintype "passive"))
      (node (ref "CONN1") (pin "9") (pinfunction "9_9") (pintype "passive"))
      (node (ref "FB6") (pin "2") (pinfunction "2_2") (pintype "passive"))
      (node (ref "R2") (pin "1") (pinfunction "1_1") (pintype "passive"))
      (node (ref "U1") (pin "7") (pinfunction "VIN-_7") (pintype "passive"))
    )
    (net (code "35") (name "/VOUT1") (class "Default")
      (node (ref "C6") (pin "P") (pinfunction "P_P") (pintype "passive"))
      (node (ref "D12") (pin "1") (pinfunction "1_1") (pintype "passive"))
      (node (ref "D12") (pin "3") (pinfunction "3_3") (pintype "passive"))
      (node (ref "D12") (pin "5") (pinfunction "5_5") (pintype "passive"))
      (node (ref "J3") (pin "2") (pinfunction "2_2") (pintype "passive"))
      (node (ref "R4") (pin "2") (pinfunction "2_2") (pintype "passive"))
      (node (ref "R9") (pin "1") (pinfunction "1_1") (pintype "passive"))
      (node (ref "TP11") (pin "1") (pinfunction "1_1") (pintype "passive"))
      (node (ref "U1") (pin "13") (pinfunction "VOUT1_13") (pintype "passive"))
      (node (ref "U1") (pin "14") (pinfunction "VOUT1_14") (pintype "passive"))
    )
    (net (code "36") (name "/VOUT2") (class "Default")
      (node (ref "C1") (pin "2") (pinfunction "2_2") (pintype "passive"))
      (node (ref "C5") (pin "P") (pinfunction "P_P") (pintype "passive"))
      (node (ref "D5") (pin "2") (pinfunction "K_2") (pintype "passive"))
      (node (ref "J3") (pin "1") (pinfunction "1_1") (pintype "passive"))
      (node (ref "Q1") (pin "1") (pinfunction "SOURCE_1") (pintype "passive"))
      (node (ref "Q1") (pin "2") (pinfunction "SOURCE_2") (pintype "passive"))
      (node (ref "Q1") (pin "3") (pinfunction "SOURCE_3") (pintype "passive"))
      (node (ref "TP1") (pin "1") (pinfunction "1_1") (pintype "passive"))
      (node (ref "U1") (pin "10") (pinfunction "VOUT2_10") (pintype "passive"))
      (node (ref "U1") (pin "9") (pinfunction "VOUT2_9") (pintype "passive"))
      (node (ref "U2") (pin "4") (pinfunction "IN_4") (pintype "input"))
    )
    (net (code "37") (name "CGND") (class "Default")
      (node (ref "C17") (pin "1") (pinfunction "1_1") (pintype "passive"))
      (node (ref "C18") (pin "1") (pinfunction "1_1") (pintype "passive"))
      (node (ref "CONN1") (pin "S1") (pinfunction "SHIELD_S1") (pintype "passive"))
      (node (ref "CONN1") (pin "S2") (pinfunction "SHIELD_S2") (pintype "passive"))
      (node (ref "CONN2") (pin "S1") (pinfunction "SHIELD_S1") (pintype "passive"))
      (node (ref "CONN2") (pin "S2") (pinfunction "SHIELD_S2") (pintype "passive"))
    )
    (net (code "38") (name "GND") (class "Default")
      (node (ref "C1") (pin "1") (pinfunction "1_1") (pintype "passive"))
      (node (ref "C19") (pin "N") (pinfunction "N_N") (pintype "passive"))
      (node (ref "C2") (pin "1") (pinfunction "1_1") (pintype "passive"))
      (node (ref "C3") (pin "1") (pinfunction "1_1") (pintype "passive"))
      (node (ref "C4") (pin "1") (pinfunction "1_1") (pintype "passive"))
      (node (ref "C6") (pin "N") (pinfunction "N_N") (pintype "passive"))
      (node (ref "C7") (pin "2") (pinfunction "2_2") (pintype "passive"))
      (node (ref "C8") (pin "2") (pinfunction "2_2") (pintype "passive"))
      (node (ref "CONN3") (pin "B") (pinfunction "B_B") (pintype "passive"))
      (node (ref "CONN3") (pin "C") (pinfunction "C_C") (pintype "passive"))
      (node (ref "D11") (pin "1") (pinfunction "A_1") (pintype "passive"))
      (node (ref "D5") (pin "1") (pinfunction "A_1") (pintype "passive"))
      (node (ref "J1") (pin "1") (pinfunction "1_1") (pintype "passive"))
      (node (ref "J2") (pin "1") (pinfunction "1_1") (pintype "passive"))
      (node (ref "J4") (pin "2") (pinfunction "2_2") (pintype "passive"))
      (node (ref "MP2") (pin "1") (pinfunction "1_1") (pintype "passive"))
      (node (ref "MP4") (pin "1") (pinfunction "1_1") (pintype "passive"))
      (node (ref "R20") (pin "1") (pinfunction "1_1") (pintype "passive"))
      (node (ref "TP7") (pin "1") (pinfunction "1_1") (pintype "passive"))
      (node (ref "U1") (pin "15") (pinfunction "0V1_15") (pintype "passive"))
      (node (ref "U1") (pin "16") (pinfunction "0V1_16") (pintype "passive"))
      (node (ref "U1") (pin "19") (pinfunction "THERM_19") (pintype "passive"))
      (node (ref "U2") (pin "2") (pinfunction "GND_2") (pintype "power_in"))
      (node (ref "U3") (pin "3") (pinfunction "3_3") (pintype "passive"))
      (node (ref "U4") (pin "3") (pinfunction "3_3") (pintype "passive"))
      (node (ref "U5") (pin "2") (pinfunction "GND_2") (pintype "power_in"))
      (node (ref "U6") (pin "3") (pinfunction "3_3") (pintype "passive"))
      (node (ref "U7") (pin "2") (pinfunction "2_2") (pintype "passive"))
    )
    (net (code "39") (name "Net-(C9-Pad2)") (class "Default")
      (node (ref "C9") (pin "2") (pinfunction "2_2") (pintype "passive"))
      (node (ref "R10") (pin "1") (pinfunction "1_1") (pintype "passive"))
    )
    (net (code "40") (name "Net-(C10-Pad1)") (class "Default")
      (node (ref "C10") (pin "1") (pinfunction "1_1") (pintype "passive"))
      (node (ref "C11") (pin "1") (pinfunction "1_1") (pintype "passive"))
      (node (ref "C12") (pin "1") (pinfunction "1_1") (pintype "passive"))
      (node (ref "C17") (pin "2") (pinfunction "2_2") (pintype "passive"))
      (node (ref "C9") (pin "1") (pinfunction "1_1") (pintype "passive"))
    )
    (net (code "41") (name "Net-(C10-Pad2)") (class "Default")
      (node (ref "C10") (pin "2") (pinfunction "2_2") (pintype "passive"))
      (node (ref "R11") (pin "1") (pinfunction "1_1") (pintype "passive"))
    )
    (net (code "42") (name "Net-(C11-Pad2)") (class "Default")
      (node (ref "C11") (pin "2") (pinfunction "2_2") (pintype "passive"))
      (node (ref "R12") (pin "1") (pinfunction "1_1") (pintype "passive"))
    )
    (net (code "43") (name "Net-(C12-Pad2)") (class "Default")
      (node (ref "C12") (pin "2") (pinfunction "2_2") (pintype "passive"))
      (node (ref "R13") (pin "1") (pinfunction "1_1") (pintype "passive"))
    )
    (net (code "44") (name "Net-(C13-Pad1)") (class "Default")
      (node (ref "C13") (pin "1") (pinfunction "1_1") (pintype "passive"))
      (node (ref "C14") (pin "1") (pinfunction "1_1") (pintype "passive"))
      (node (ref "C15") (pin "1") (pinfunction "1_1") (pintype "passive"))
      (node (ref "C16") (pin "1") (pinfunction "1_1") (pintype "passive"))
      (node (ref "C18") (pin "2") (pinfunction "2_2") (pintype "passive"))
    )
    (net (code "45") (name "Net-(C13-Pad2)") (class "Default")
      (node (ref "C13") (pin "2") (pinfunction "2_2") (pintype "passive"))
      (node (ref "R14") (pin "1") (pinfunction "1_1") (pintype "passive"))
    )
    (net (code "46") (name "Net-(C14-Pad2)") (class "Default")
      (node (ref "C14") (pin "2") (pinfunction "2_2") (pintype "passive"))
      (node (ref "R15") (pin "1") (pinfunction "1_1") (pintype "passive"))
    )
    (net (code "47") (name "Net-(C15-Pad2)") (class "Default")
      (node (ref "C15") (pin "2") (pinfunction "2_2") (pintype "passive"))
      (node (ref "R16") (pin "1") (pinfunction "1_1") (pintype "passive"))
    )
    (net (code "48") (name "Net-(C16-Pad2)") (class "Default")
      (node (ref "C16") (pin "2") (pinfunction "2_2") (pintype "passive"))
      (node (ref "R17") (pin "1") (pinfunction "1_1") (pintype "passive"))
    )
    (net (code "49") (name "Net-(D1-K)") (class "Default")
      (node (ref "D1") (pin "2") (pinfunction "K_2") (pintype "passive"))
      (node (ref "D2") (pin "1") (pinfunction "A_1") (pintype "passive"))
      (node (ref "R12") (pin "2") (pinfunction "2_2") (pintype "passive"))
      (node (ref "T1") (pin "18") (pinfunction "CX3_18") (pintype "passive"))
    )
    (net (code "50") (name "Net-(D3-A)") (class "Default")
      (node (ref "D3") (pin "1") (pinfunction "A_1") (pintype "passive"))
      (node (ref "D4") (pin "2") (pinfunction "K_2") (pintype "passive"))
      (node (ref "R13") (pin "2") (pinfunction "2_2") (pintype "passive"))
      (node (ref "T1") (pin "15") (pinfunction "CX4_15") (pintype "passive"))
    )
    (net (code "51") (name "Net-(D7-K)") (class "Default")
      (node (ref "D7") (pin "2") (pinfunction "K_2") (pintype "passive"))
      (node (ref "D8") (pin "1") (pinfunction "A_1") (pintype "passive"))
      (node (ref "R10") (pin "2") (pinfunction "2_2") (pintype "passive"))
      (node (ref "T1") (pin "24") (pinfunction "CX1_24") (pintype "passive"))
    )
    (net (code "52") (name "Net-(D10-K)") (class "Default")
      (node (ref "D10") (pin "2") (pinfunction "K_2") (pintype "passive"))
      (node (ref "D9") (pin "1") (pinfunction "A_1") (pintype "passive"))
      (node (ref "R11") (pin "2") (pinfunction "2_2") (pintype "passive"))
      (node (ref "T1") (pin "21") (pinfunction "CX2_21") (pintype "passive"))
    )
    (net (code "53") (name "Net-(D12-Pad2)") (class "Default")
      (node (ref "D12") (pin "2") (pinfunction "2_2") (pintype "passive"))
      (node (ref "R6") (pin "1") (pinfunction "1_1") (pintype "passive"))
    )
    (net (code "54") (name "Net-(D12-Pad4)") (class "Default")
      (node (ref "D12") (pin "4") (pinfunction "4_4") (pintype "passive"))
      (node (ref "R8") (pin "1") (pinfunction "1_1") (pintype "passive"))
    )
    (net (code "55") (name "Net-(D12-Pad6)") (class "Default")
      (node (ref "D12") (pin "6") (pinfunction "6_6") (pintype "passive"))
      (node (ref "R5") (pin "1") (pinfunction "1_1") (pintype "passive"))
    )
    (net (code "56") (name "Net-(FB1-Pad2)") (class "Default")
      (node (ref "FB1") (pin "2") (pinfunction "2_2") (pintype "passive"))
      (node (ref "FB2") (pin "1") (pinfunction "1_1") (pintype "passive"))
    )
    (net (code "57") (name "Net-(FB2-Pad2)") (class "Default")
      (node (ref "FB2") (pin "2") (pinfunction "2_2") (pintype "passive"))
      (node (ref "FB3") (pin "1") (pinfunction "1_1") (pintype "passive"))
    )
    (net (code "58") (name "Net-(FB4-Pad2)") (class "Default")
      (node (ref "FB4") (pin "2") (pinfunction "2_2") (pintype "passive"))
      (node (ref "FB5") (pin "1") (pinfunction "1_1") (pintype "passive"))
    )
    (net (code "59") (name "Net-(FB5-Pad2)") (class "Default")
      (node (ref "FB5") (pin "2") (pinfunction "2_2") (pintype "passive"))
      (node (ref "FB6") (pin "1") (pinfunction "1_1") (pintype "passive"))
    )
    (net (code "60") (name "Net-(Q1-GATE)") (class "Default")
      (node (ref "Q1") (pin "4") (pinfunction "GATE_4") (pintype "passive"))
      (node (ref "U2") (pin "5") (pinfunction "GATE_5") (pintype "output"))
    )
    (net (code "61") (name "Net-(Q2-GATE)") (class "Default")
      (node (ref "Q2") (pin "4") (pinfunction "GATE_4") (pintype "passive"))
      (node (ref "U5") (pin "5") (pinfunction "GATE_5") (pintype "output"))
    )
    (net (code "62") (name "Net-(R7-Pad2)") (class "Default")
      (node (ref "R7") (pin "2") (pinfunction "2_2") (pintype "passive"))
      (node (ref "U8") (pin "1") (pinfunction "1_1") (pintype "passive"))
    )
    (net (code "63") (name "Net-(R18-Pad1)") (class "Default")
      (node (ref "R18") (pin "1") (pinfunction "1_1") (pintype "passive"))
      (node (ref "U7") (pin "4") (pinfunction "4_4") (pintype "passive"))
    )
    (net (code "64") (name "Net-(R19-Pad1)") (class "Default")
      (node (ref "R19") (pin "1") (pinfunction "1_1") (pintype "passive"))
      (node (ref "U8") (pin "4") (pinfunction "4_4") (pintype "passive"))
    )
    (net (code "65") (name "Net-(T1-CD1)") (class "Default")
      (node (ref "R17") (pin "2") (pinfunction "2_2") (pintype "passive"))
      (node (ref "T1") (pin "1") (pinfunction "CD1_1") (pintype "passive"))
    )
    (net (code "66") (name "Net-(T1-CD2)") (class "Default")
      (node (ref "R16") (pin "2") (pinfunction "2_2") (pintype "passive"))
      (node (ref "T1") (pin "4") (pinfunction "CD2_4") (pintype "passive"))
    )
    (net (code "67") (name "Net-(T1-CD3)") (class "Default")
      (node (ref "R15") (pin "2") (pinfunction "2_2") (pintype "passive"))
      (node (ref "T1") (pin "7") (pinfunction "CD3_7") (pintype "passive"))
    )
    (net (code "68") (name "Net-(T1-CD4)") (class "Default")
      (node (ref "R14") (pin "2") (pinfunction "2_2") (pintype "passive"))
      (node (ref "T1") (pin "10") (pinfunction "CD4_10") (pintype "passive"))
    )
    (net (code "69") (name "Net-(U1-ADJ)") (class "Default")
      (node (ref "R20") (pin "2") (pinfunction "2_2") (pintype "passive"))
      (node (ref "R9") (pin "2") (pinfunction "2_2") (pintype "passive"))
      (node (ref "U1") (pin "17") (pinfunction "ADJ_17") (pintype "passive"))
    )
    (net (code "70") (name "Net-(U1-PoH_En)") (class "Default")
      (node (ref "R2") (pin "2") (pinfunction "2_2") (pintype "passive"))
      (node (ref "U1") (pin "6") (pinfunction "PoH_En_6") (pintype "passive"))
    )
    (net (code "71") (name "Net-(U2-OFF)") (class "Default")
      (node (ref "TP9") (pin "1") (pinfunction "1_1") (pintype "passive"))
      (node (ref "U2") (pin "3") (pinfunction "OFF_3") (pintype "input"))
    )
    (net (code "72") (name "Net-(U2-VS)") (class "Default")
      (node (ref "C2") (pin "2") (pinfunction "2_2") (pintype "passive"))
      (node (ref "R1") (pin "1") (pinfunction "1_1") (pintype "passive"))
      (node (ref "U2") (pin "1") (pinfunction "VS_1") (pintype "power_in"))
    )
    (net (code "73") (name "Net-(U5-OFF)") (class "Default")
      (node (ref "TP10") (pin "1") (pinfunction "1_1") (pintype "passive"))
      (node (ref "U5") (pin "3") (pinfunction "OFF_3") (pintype "input"))
    )
    (net (code "74") (name "Net-(U5-VS)") (class "Default")
      (node (ref "C4") (pin "2") (pinfunction "2_2") (pintype "passive"))
      (node (ref "R3") (pin "1") (pinfunction "1_1") (pintype "passive"))
      (node (ref "U5") (pin "1") (pinfunction "VS_1") (pintype "power_in"))
    )
    (net (code "75") (name "VCC") (class "Default")
      (node (ref "C19") (pin "P") (pinfunction "P_P") (pintype "passive"))
      (node (ref "J1") (pin "2") (pinfunction "2_2") (pintype "passive"))
      (node (ref "Q1") (pin "5") (pinfunction "DRAIN_5") (pintype "passive"))
      (node (ref "Q1") (pin "6") (pinfunction "DRAIN_6") (pintype "passive"))
      (node (ref "Q1") (pin "7") (pinfunction "DRAIN_7") (pintype "passive"))
      (node (ref "Q1") (pin "8") (pinfunction "DRAIN_8") (pintype "passive"))
      (node (ref "Q2") (pin "5") (pinfunction "DRAIN_5") (pintype "passive"))
      (node (ref "Q2") (pin "6") (pinfunction "DRAIN_6") (pintype "passive"))
      (node (ref "Q2") (pin "7") (pinfunction "DRAIN_7") (pintype "passive"))
      (node (ref "Q2") (pin "8") (pinfunction "DRAIN_8") (pintype "passive"))
      (node (ref "R1") (pin "2") (pinfunction "2_2") (pintype "passive"))
      (node (ref "R3") (pin "2") (pinfunction "2_2") (pintype "passive"))
      (node (ref "TP6") (pin "1") (pinfunction "1_1") (pintype "passive"))
      (node (ref "U2") (pin "6") (pinfunction "OUT_6") (pintype "output"))
      (node (ref "U5") (pin "6") (pinfunction "OUT_6") (pintype "output"))
    )
    (net (code "76") (name "unconnected-(CONN2-Pad9)") (class "Default")
      (node (ref "CONN2") (pin "9") (pinfunction "9_9") (pintype "passive"))
    )
    (net (code "77") (name "unconnected-(CONN2-Pad10)") (class "Default")
      (node (ref "CONN2") (pin "10") (pinfunction "10_10") (pintype "passive"))
    )
    (net (code "78") (name "unconnected-(CONN2-Pad11)") (class "Default")
      (node (ref "CONN2") (pin "11") (pinfunction "11_11") (pintype "passive"))
    )
    (net (code "79") (name "unconnected-(CONN2-Pad12)") (class "Default")
      (node (ref "CONN2") (pin "12") (pinfunction "12_12") (pintype "passive"))
    )
    (net (code "80") (name "unconnected-(J4-Pad3)") (class "Default")
      (node (ref "J4") (pin "3") (pinfunction "3_3") (pintype "passive+no_connect"))
    )
    (net (code "81") (name "unconnected-(MP1-Pad1)") (class "Default")
      (node (ref "MP1") (pin "1") (pinfunction "1_1") (pintype "passive"))
    )
    (net (code "82") (name "unconnected-(MP3-Pad1)") (class "Default")
      (node (ref "MP3") (pin "1") (pinfunction "1_1") (pintype "passive"))
    )
    (net (code "83") (name "unconnected-(U1-SA1-Pad1)") (class "Default")
      (node (ref "U1") (pin "1") (pinfunction "SA1_1") (pintype "passive+no_connect"))
    )
    (net (code "84") (name "unconnected-(U1-SA2-Pad2)") (class "Default")
      (node (ref "U1") (pin "2") (pinfunction "SA2_2") (pintype "passive+no_connect"))
    )
  )
)
